# 04_-_PMIC-PWR_Monitor.net
KiCad netlist of a schematic drawn in Altium Designer
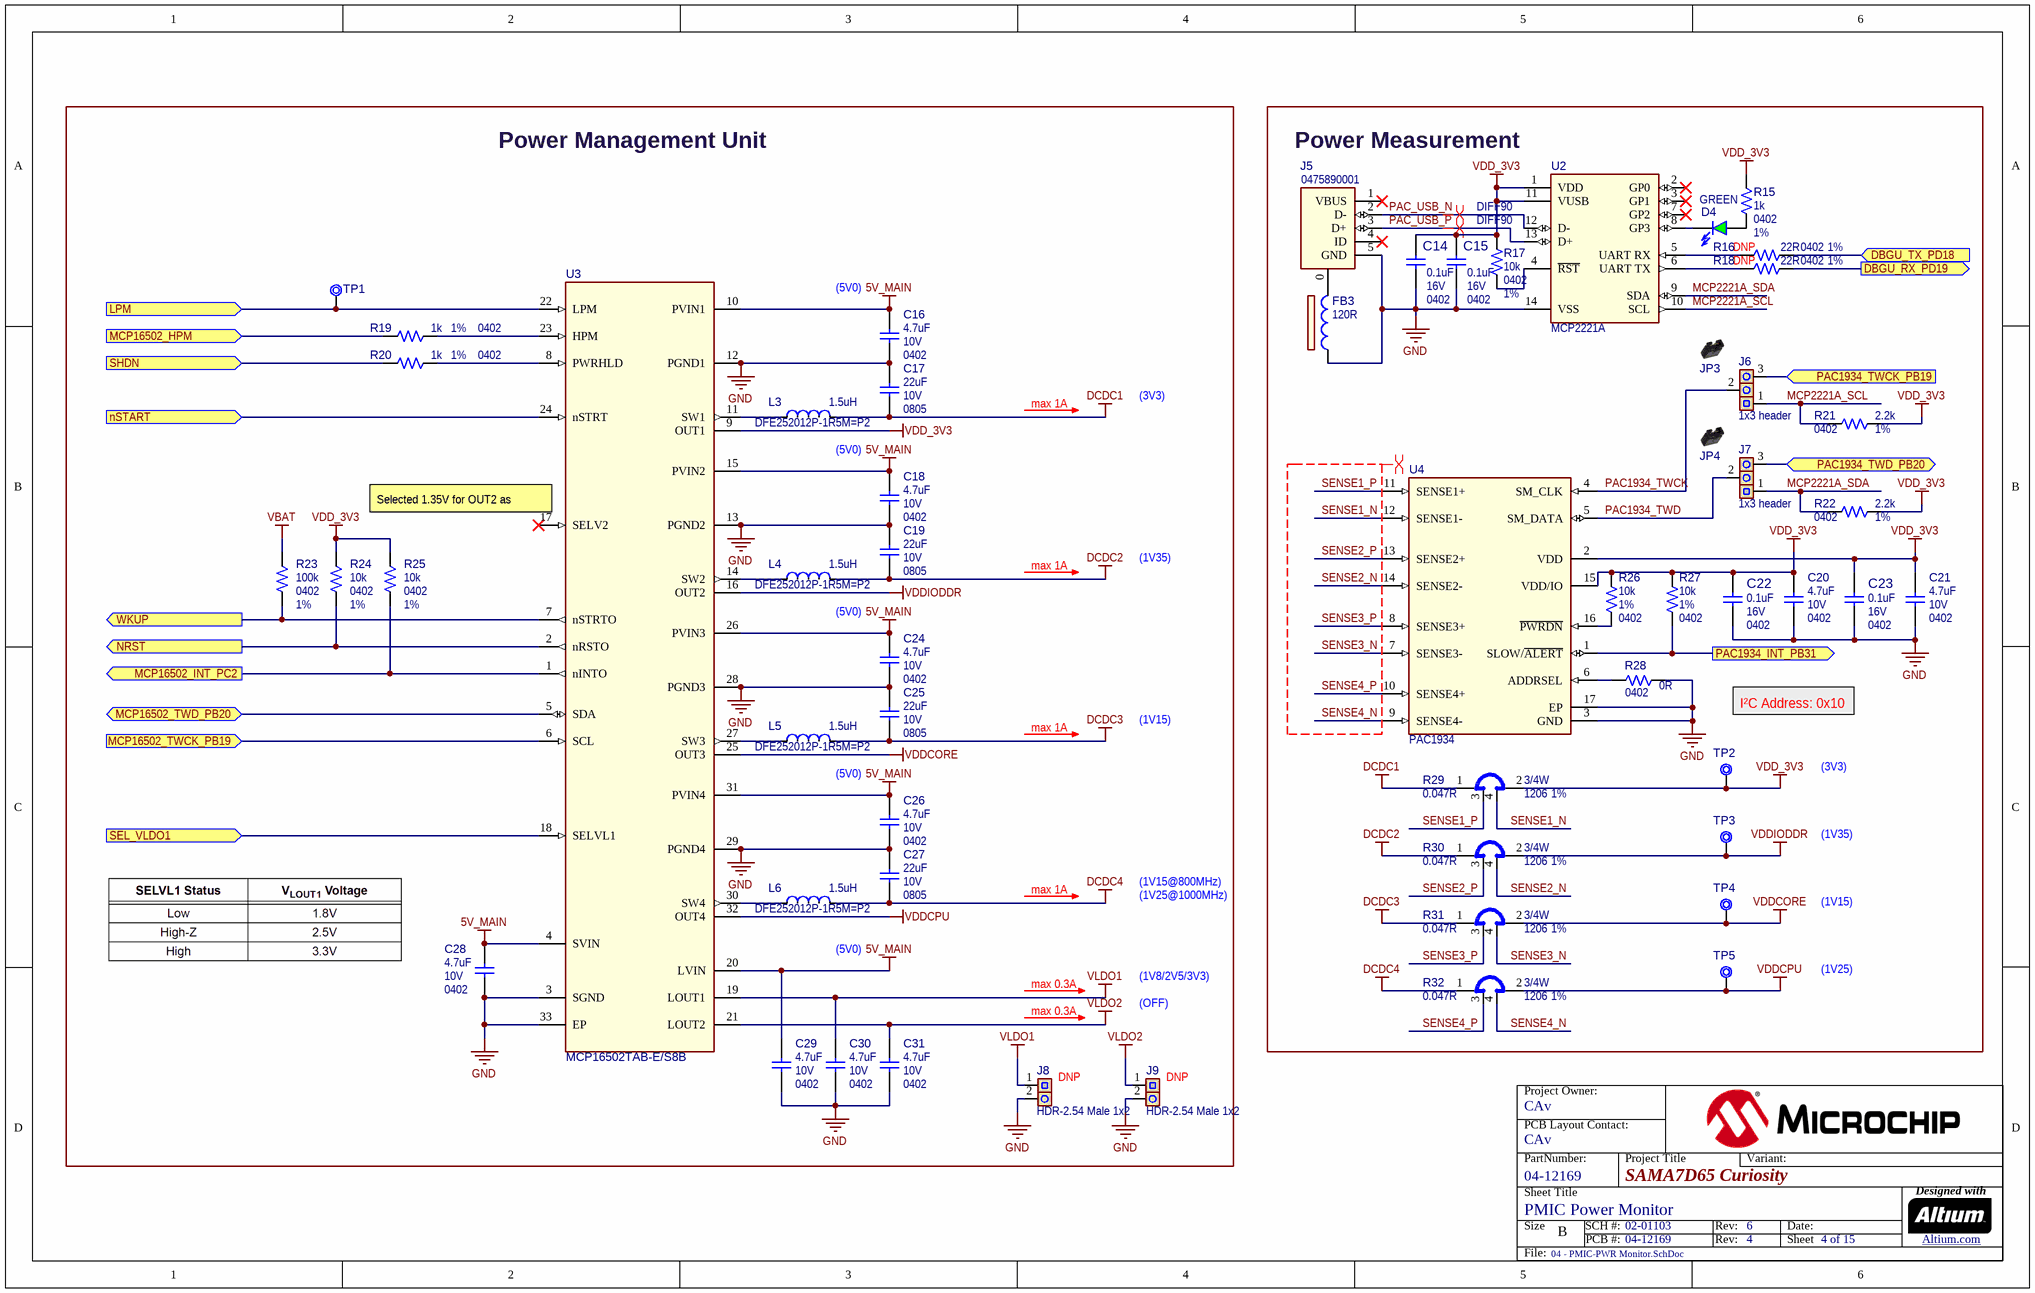
[diagram p0: 04 - PMIC-PWR Monitor.SchDoc]

(export (version "E")
  (design (tool "Eeschema 10.0.6"))
  (components
    (comp (ref "C14")
      (value "0.1uF")
      (footprint "CAP_C_0402")
      (fields
        (field (name "VOLTAGE") "16V")
        (field (name "PACKAGE") "0402")
        (field (name "TOLERANCE") "10%")
        (field (name "Comment") "Capacitor NP")
        (field (name "OWNER") "Sompoch Loboonlert")
      )
      (libsource (lib "MCHP-CDB") (part "Capacitor NP"))
    )
    (comp (ref "C15")
      (value "0.1uF")
      (footprint "CAP_C_0402")
      (fields
        (field (name "VOLTAGE") "16V")
        (field (name "PACKAGE") "0402")
        (field (name "TOLERANCE") "10%")
        (field (name "Comment") "Capacitor NP")
        (field (name "OWNER") "Sompoch Loboonlert")
      )
      (libsource (lib "MCHP-CDB") (part "Capacitor NP"))
    )
    (comp (ref "C16")
      (value "4.7uF")
      (footprint "CAP_C_0402")
      (description "Capacitor")
      (fields
        (field (name "VOLTAGE") "10V")
        (field (name "PACKAGE") "0402")
        (field (name "TOLERANCE") "10%")
        (field (name "Comment") "Capacitor NP")
        (field (name "OWNER") "Jesus Aviles")
      )
      (libsource (lib "") (part "Capacitor NP_1"))
    )
    (comp (ref "C17")
      (value "22uF")
      (footprint "CAP_C_0805")
      (fields
        (field (name "VOLTAGE") "10V")
        (field (name "PACKAGE") "0805")
        (field (name "TOLERANCE") "20%")
        (field (name "Comment") "Capacitor NP")
        (field (name "OWNER") "Razvan Cristescu")
      )
      (libsource (lib "MCHP-CDB") (part "Capacitor NP"))
    )
    (comp (ref "C18")
      (value "4.7uF")
      (footprint "CAP_C_0402")
      (description "Capacitor")
      (fields
        (field (name "VOLTAGE") "10V")
        (field (name "PACKAGE") "0402")
        (field (name "TOLERANCE") "10%")
        (field (name "Comment") "Capacitor NP")
        (field (name "OWNER") "Jesus Aviles")
      )
      (libsource (lib "") (part "Capacitor NP_1"))
    )
    (comp (ref "C19")
      (value "22uF")
      (footprint "CAP_C_0805")
      (fields
        (field (name "VOLTAGE") "10V")
        (field (name "PACKAGE") "0805")
        (field (name "TOLERANCE") "20%")
        (field (name "Comment") "Capacitor NP")
        (field (name "OWNER") "Razvan Cristescu")
      )
      (libsource (lib "MCHP-CDB") (part "Capacitor NP"))
    )
    (comp (ref "C20")
      (value "4.7uF")
      (footprint "CAP_C_0402")
      (description "Capacitor")
      (fields
        (field (name "VOLTAGE") "10V")
        (field (name "PACKAGE") "0402")
        (field (name "TOLERANCE") "10%")
        (field (name "Comment") "Capacitor NP")
        (field (name "OWNER") "Jesus Aviles")
      )
      (libsource (lib "") (part "Capacitor NP_1"))
    )
    (comp (ref "C21")
      (value "4.7uF")
      (footprint "CAP_C_0402")
      (description "Capacitor")
      (fields
        (field (name "VOLTAGE") "10V")
        (field (name "PACKAGE") "0402")
        (field (name "TOLERANCE") "10%")
        (field (name "Comment") "Capacitor NP")
        (field (name "OWNER") "Jesus Aviles")
      )
      (libsource (lib "") (part "Capacitor NP_1"))
    )
    (comp (ref "C22")
      (value "0.1uF")
      (footprint "CAP_C_0402")
      (fields
        (field (name "VOLTAGE") "16V")
        (field (name "PACKAGE") "0402")
        (field (name "TOLERANCE") "10%")
        (field (name "Comment") "Capacitor NP")
        (field (name "OWNER") "Sompoch Loboonlert")
      )
      (libsource (lib "MCHP-CDB") (part "Capacitor NP"))
    )
    (comp (ref "C23")
      (value "0.1uF")
      (footprint "CAP_C_0402")
      (fields
        (field (name "VOLTAGE") "16V")
        (field (name "PACKAGE") "0402")
        (field (name "TOLERANCE") "10%")
        (field (name "Comment") "Capacitor NP")
        (field (name "OWNER") "Sompoch Loboonlert")
      )
      (libsource (lib "MCHP-CDB") (part "Capacitor NP"))
    )
    (comp (ref "C24")
      (value "4.7uF")
      (footprint "CAP_C_0402")
      (description "Capacitor")
      (fields
        (field (name "VOLTAGE") "10V")
        (field (name "PACKAGE") "0402")
        (field (name "TOLERANCE") "10%")
        (field (name "Comment") "Capacitor NP")
        (field (name "OWNER") "Jesus Aviles")
      )
      (libsource (lib "") (part "Capacitor NP_1"))
    )
    (comp (ref "C25")
      (value "22uF")
      (footprint "CAP_C_0805")
      (fields
        (field (name "VOLTAGE") "10V")
        (field (name "PACKAGE") "0805")
        (field (name "TOLERANCE") "20%")
        (field (name "Comment") "Capacitor NP")
        (field (name "OWNER") "Razvan Cristescu")
      )
      (libsource (lib "MCHP-CDB") (part "Capacitor NP"))
    )
    (comp (ref "C26")
      (value "4.7uF")
      (footprint "CAP_C_0402")
      (description "Capacitor")
      (fields
        (field (name "VOLTAGE") "10V")
        (field (name "PACKAGE") "0402")
        (field (name "TOLERANCE") "10%")
        (field (name "Comment") "Capacitor NP")
        (field (name "OWNER") "Jesus Aviles")
      )
      (libsource (lib "") (part "Capacitor NP_1"))
    )
    (comp (ref "C27")
      (value "22uF")
      (footprint "CAP_C_0805")
      (fields
        (field (name "VOLTAGE") "10V")
        (field (name "PACKAGE") "0805")
        (field (name "TOLERANCE") "20%")
        (field (name "Comment") "Capacitor NP")
        (field (name "OWNER") "Razvan Cristescu")
      )
      (libsource (lib "MCHP-CDB") (part "Capacitor NP"))
    )
    (comp (ref "C28")
      (value "4.7uF")
      (footprint "CAP_C_0402")
      (description "Capacitor")
      (fields
        (field (name "VOLTAGE") "10V")
        (field (name "PACKAGE") "0402")
        (field (name "TOLERANCE") "10%")
        (field (name "Comment") "Capacitor NP")
        (field (name "OWNER") "Jesus Aviles")
      )
      (libsource (lib "") (part "Capacitor NP_1"))
    )
    (comp (ref "C29")
      (value "4.7uF")
      (footprint "CAP_C_0402")
      (description "Capacitor")
      (fields
        (field (name "VOLTAGE") "10V")
        (field (name "PACKAGE") "0402")
        (field (name "TOLERANCE") "10%")
        (field (name "Comment") "Capacitor NP")
        (field (name "OWNER") "Jesus Aviles")
      )
      (libsource (lib "") (part "Capacitor NP_1"))
    )
    (comp (ref "C30")
      (value "4.7uF")
      (footprint "CAP_C_0402")
      (description "Capacitor")
      (fields
        (field (name "VOLTAGE") "10V")
        (field (name "PACKAGE") "0402")
        (field (name "TOLERANCE") "10%")
        (field (name "Comment") "Capacitor NP")
        (field (name "OWNER") "Jesus Aviles")
      )
      (libsource (lib "") (part "Capacitor NP_1"))
    )
    (comp (ref "C31")
      (value "4.7uF")
      (footprint "CAP_C_0402")
      (description "Capacitor")
      (fields
        (field (name "VOLTAGE") "10V")
        (field (name "PACKAGE") "0402")
        (field (name "TOLERANCE") "10%")
        (field (name "Comment") "Capacitor NP")
        (field (name "OWNER") "Jesus Aviles")
      )
      (libsource (lib "") (part "Capacitor NP_1"))
    )
    (comp (ref "D4")
      (value "GREEN")
      (footprint "LED_0603_GREEN")
      (description "LED")
      (fields
        (field (name "POWER") "75mW")
        (field (name "Comment") "LED_green")
        (field (name "OWNER") "Tad Ahlvers")
      )
      (libsource (lib "MCHP-CDB") (part "LED_green"))
    )
    (comp (ref "FB3")
      (value "120R")
      (footprint "IND_C_0603")
      (fields (field (name "Comment") "Ferrite Bead") (field (name "OWNER") "Petnarong Chaijaroong"))
      (libsource (lib "MCHP-CDB") (part "Ferrite Bead"))
    )
    (comp (ref "J5")
      (value "0475890001")
      (footprint "CON_USB_Micro-AB_SMD_RA_MOLEX_0475890001")
      (fields
        (field (name "VOLTAGE") "30VAC")
        (field (name "Comment") "CON USB2.0 Mini_Micro")
        (field (name "OWNER") "Dragos Danaila")
      )
      (libsource (lib "MCHP-CDB") (part "CON USB2.0 Mini_Micro"))
    )
    (comp (ref "J6")
      (value "1x3 header")
      (footprint "HDR_M_2.54_1x3")
      (fields (field (name "Comment") "Header 1x3") (field (name "OWNER") "Dragos Danaila"))
      (libsource (lib "MCHP-CDB") (part "Header 1x3"))
    )
    (comp (ref "J7")
      (value "1x3 header")
      (footprint "HDR_M_2.54_1x3")
      (fields (field (name "Comment") "Header 1x3") (field (name "OWNER") "Dragos Danaila"))
      (libsource (lib "MCHP-CDB") (part "Header 1x3"))
    )
    (comp (ref "J8")
      (value "HDR-2.54 Male 1x2")
      (footprint "HDR_M_2.54_1x2")
      (fields
        (field (name "POPULATED") "DNP")
        (field (name "VOLTAGE") "250V")
        (field (name "Comment") "Header 1x2")
        (field (name "OWNER") "Narasimha Murthy")
      )
      (libsource (lib "MCHP-CDB") (part "Header 1x2"))
    )
    (comp (ref "J9")
      (value "HDR-2.54 Male 1x2")
      (footprint "HDR_M_2.54_1x2")
      (fields
        (field (name "POPULATED") "DNP")
        (field (name "VOLTAGE") "250V")
        (field (name "Comment") "Header 1x2")
        (field (name "OWNER") "Narasimha Murthy")
      )
      (libsource (lib "MCHP-CDB") (part "Header 1x2"))
    )
    (comp (ref "JP3")
      (value "Jumper Mechanical")
      (footprint "Jumper_Mechanical")
      (fields (field (name "OWNER") "Narasimha Murthy"))
      (libsource (lib "MCHP-CDB") (part "Jumper Mechanical"))
    )
    (comp (ref "JP4")
      (value "Jumper Mechanical")
      (footprint "Jumper_Mechanical")
      (fields (field (name "OWNER") "Narasimha Murthy"))
      (libsource (lib "MCHP-CDB") (part "Jumper Mechanical"))
    )
    (comp (ref "L3")
      (value "1.5uH")
      (footprint "IND_C_1008")
      (description "Inductor")
      (fields
        (field (name "MANUFACTURER PART NUMBER 1") "DFE252012P-1R5M=P2")
        (field (name "OWNER") "Razvan Cristescu")
      )
      (libsource (lib "MCHP-CDB") (part "Inductor"))
    )
    (comp (ref "L4")
      (value "1.5uH")
      (footprint "IND_C_1008")
      (description "Inductor")
      (fields
        (field (name "MANUFACTURER PART NUMBER 1") "DFE252012P-1R5M=P2")
        (field (name "OWNER") "Razvan Cristescu")
      )
      (libsource (lib "MCHP-CDB") (part "Inductor"))
    )
    (comp (ref "L5")
      (value "1.5uH")
      (footprint "IND_C_1008")
      (description "Inductor")
      (fields
        (field (name "MANUFACTURER PART NUMBER 1") "DFE252012P-1R5M=P2")
        (field (name "OWNER") "Razvan Cristescu")
      )
      (libsource (lib "MCHP-CDB") (part "Inductor"))
    )
    (comp (ref "L6")
      (value "1.5uH")
      (footprint "IND_C_1008")
      (description "Inductor")
      (fields
        (field (name "MANUFACTURER PART NUMBER 1") "DFE252012P-1R5M=P2")
        (field (name "OWNER") "Razvan Cristescu")
      )
      (libsource (lib "MCHP-CDB") (part "Inductor"))
    )
    (comp (ref "R15")
      (value "1k")
      (footprint "RES_C_0402")
      (description "Resistor")
      (fields
        (field (name "PACKAGE") "0402")
        (field (name "TOLERANCE") "1%")
        (field (name "VOLTAGE") "50V")
        (field (name "POWER") "1/10W")
        (field (name "OWNER") "Tad Ahlvers")
      )
      (libsource (lib "") (part "Resistor_1"))
    )
    (comp (ref "R16")
      (value "22R")
      (footprint "RES_C_0402")
      (description "Resistor")
      (fields
        (field (name "PACKAGE") "0402")
        (field (name "TOLERANCE") "1%")
        (field (name "POWER") "1/10W")
        (field (name "POPULATED") "DNP")
        (field (name "OWNER") "Mike Ragsdale")
      )
      (libsource (lib "MCHP-CDB") (part "Resistor"))
    )
    (comp (ref "R17")
      (value "10k")
      (footprint "RES_C_0402")
      (description "Resistor")
      (fields
        (field (name "PACKAGE") "0402")
        (field (name "TOLERANCE") "1%")
        (field (name "POWER") "1/10W")
        (field (name "VOLTAGE") "50V")
        (field (name "OWNER") "Brent Lanphear")
      )
      (libsource (lib "MCHP-CDB") (part "Resistor"))
    )
    (comp (ref "R18")
      (value "22R")
      (footprint "RES_C_0402")
      (description "Resistor")
      (fields
        (field (name "PACKAGE") "0402")
        (field (name "TOLERANCE") "1%")
        (field (name "POWER") "1/10W")
        (field (name "POPULATED") "DNP")
        (field (name "OWNER") "Mike Ragsdale")
      )
      (libsource (lib "MCHP-CDB") (part "Resistor"))
    )
    (comp (ref "R19")
      (value "1k")
      (footprint "RES_C_0402")
      (description "Resistor")
      (fields
        (field (name "PACKAGE") "0402")
        (field (name "TOLERANCE") "1%")
        (field (name "VOLTAGE") "50V")
        (field (name "POWER") "1/10W")
        (field (name "OWNER") "Tad Ahlvers")
      )
      (libsource (lib "") (part "Resistor_1"))
    )
    (comp (ref "R20")
      (value "1k")
      (footprint "RES_C_0402")
      (description "Resistor")
      (fields
        (field (name "PACKAGE") "0402")
        (field (name "TOLERANCE") "1%")
        (field (name "VOLTAGE") "50V")
        (field (name "POWER") "1/10W")
        (field (name "OWNER") "Tad Ahlvers")
      )
      (libsource (lib "") (part "Resistor_1"))
    )
    (comp (ref "R21")
      (value "2.2k")
      (footprint "RES_C_0402")
      (description "Resistor")
      (fields
        (field (name "PACKAGE") "0402")
        (field (name "TOLERANCE") "1%")
        (field (name "VOLTAGE") "50V")
        (field (name "POWER") "1/10W")
        (field (name "OWNER") "Tad Ahlvers")
      )
      (libsource (lib "MCHP-CDB") (part "Resistor"))
    )
    (comp (ref "R22")
      (value "2.2k")
      (footprint "RES_C_0402")
      (description "Resistor")
      (fields
        (field (name "PACKAGE") "0402")
        (field (name "TOLERANCE") "1%")
        (field (name "VOLTAGE") "50V")
        (field (name "POWER") "1/10W")
        (field (name "OWNER") "Tad Ahlvers")
      )
      (libsource (lib "MCHP-CDB") (part "Resistor"))
    )
    (comp (ref "R23")
      (value "100k")
      (footprint "RES_C_0402")
      (description "Resistor")
      (fields
        (field (name "PACKAGE") "0402")
        (field (name "TOLERANCE") "1%")
        (field (name "VOLTAGE") "50V")
        (field (name "POWER") "1/10W")
        (field (name "OWNER") "Tad Ahlvers")
      )
      (libsource (lib "") (part "Resistor_1"))
    )
    (comp (ref "R24")
      (value "10k")
      (footprint "RES_C_0402")
      (description "Resistor")
      (fields
        (field (name "PACKAGE") "0402")
        (field (name "TOLERANCE") "1%")
        (field (name "VOLTAGE") "50V")
        (field (name "POWER") "1/10W")
        (field (name "OWNER") "Brent Lanphear")
      )
      (libsource (lib "") (part "Resistor_1"))
    )
    (comp (ref "R25")
      (value "10k")
      (footprint "RES_C_0402")
      (description "Resistor")
      (fields
        (field (name "PACKAGE") "0402")
        (field (name "TOLERANCE") "1%")
        (field (name "VOLTAGE") "50V")
        (field (name "POWER") "1/10W")
        (field (name "OWNER") "Brent Lanphear")
      )
      (libsource (lib "") (part "Resistor_1"))
    )
    (comp (ref "R26")
      (value "10k")
      (footprint "RES_C_0402")
      (description "Resistor")
      (fields
        (field (name "PACKAGE") "0402")
        (field (name "TOLERANCE") "1%")
        (field (name "VOLTAGE") "50V")
        (field (name "POWER") "1/10W")
        (field (name "OWNER") "Brent Lanphear")
      )
      (libsource (lib "MCHP-CDB") (part "Resistor"))
    )
    (comp (ref "R27")
      (value "10k")
      (footprint "RES_C_0402")
      (description "Resistor")
      (fields
        (field (name "PACKAGE") "0402")
        (field (name "TOLERANCE") "1%")
        (field (name "VOLTAGE") "50V")
        (field (name "POWER") "1/10W")
        (field (name "OWNER") "Brent Lanphear")
      )
      (libsource (lib "MCHP-CDB") (part "Resistor"))
    )
    (comp (ref "R28")
      (value "0R")
      (footprint "RES_C_0402")
      (description "Resistor")
      (fields
        (field (name "PACKAGE") "0402")
        (field (name "POWER") "1/16W")
        (field (name "OWNER") "Sompoch Loboonlert")
      )
      (libsource (lib "") (part "Resistor_1"))
    )
    (comp (ref "R29")
      (value "0.047R")
      (footprint "RES_C_1206_SHUNT")
      (description "Shunt")
      (fields
        (field (name "PACKAGE") "1206")
        (field (name "TOLERANCE") "1%")
        (field (name "POWER") "3/4W")
        (field (name "Comment") "Shunt 4 Pin")
        (field (name "OWNER") "Ciprian Abramov")
      )
      (libsource (lib "MCHP-CDB") (part "Shunt 4 Pin"))
    )
    (comp (ref "R30")
      (value "0.047R")
      (footprint "RES_C_1206_SHUNT")
      (description "Shunt")
      (fields
        (field (name "PACKAGE") "1206")
        (field (name "TOLERANCE") "1%")
        (field (name "POWER") "3/4W")
        (field (name "Comment") "Shunt 4 Pin")
        (field (name "OWNER") "Ciprian Abramov")
      )
      (libsource (lib "MCHP-CDB") (part "Shunt 4 Pin"))
    )
    (comp (ref "R31")
      (value "0.047R")
      (footprint "RES_C_1206_SHUNT")
      (description "Shunt")
      (fields
        (field (name "PACKAGE") "1206")
        (field (name "TOLERANCE") "1%")
        (field (name "POWER") "3/4W")
        (field (name "Comment") "Shunt 4 Pin")
        (field (name "OWNER") "Ciprian Abramov")
      )
      (libsource (lib "MCHP-CDB") (part "Shunt 4 Pin"))
    )
    (comp (ref "R32")
      (value "0.047R")
      (footprint "RES_C_1206_SHUNT")
      (description "Shunt")
      (fields
        (field (name "PACKAGE") "1206")
        (field (name "TOLERANCE") "1%")
        (field (name "POWER") "3/4W")
        (field (name "Comment") "Shunt 4 Pin")
        (field (name "OWNER") "Ciprian Abramov")
      )
      (libsource (lib "MCHP-CDB") (part "Shunt 4 Pin"))
    )
    (comp (ref "TP1")
      (value "Test Point No BOM")
      (footprint "TP_1mm_SMD")
      (description "Test Point")
      (fields (field (name "OWNER") "Cristian Papuc"))
      (libsource (lib "MCHP-CDB") (part "Test Point No BOM"))
    )
    (comp (ref "TP2")
      (value "Test Point No BOM")
      (footprint "TP_1mm_SMD")
      (description "Test Point")
      (fields (field (name "OWNER") "Cristian Papuc"))
      (libsource (lib "MCHP-CDB") (part "Test Point No BOM"))
    )
    (comp (ref "TP3")
      (value "Test Point No BOM")
      (footprint "TP_1mm_SMD")
      (description "Test Point")
      (fields (field (name "OWNER") "Cristian Papuc"))
      (libsource (lib "MCHP-CDB") (part "Test Point No BOM"))
    )
    (comp (ref "TP4")
      (value "Test Point No BOM")
      (footprint "TP_1mm_SMD")
      (description "Test Point")
      (fields (field (name "OWNER") "Cristian Papuc"))
      (libsource (lib "MCHP-CDB") (part "Test Point No BOM"))
    )
    (comp (ref "TP5")
      (value "Test Point No BOM")
      (footprint "TP_1mm_SMD")
      (description "Test Point")
      (fields (field (name "OWNER") "Cristian Papuc"))
      (libsource (lib "MCHP-CDB") (part "Test Point No BOM"))
    )
    (comp (ref "U2")
      (value "MCP2221A")
      (footprint "SOIC-14")
      (fields
        (field (name "Comment") "MCP2221 SOIC-14_TSSOP-14_PDIP-14")
        (field (name "OWNER") "Octavian Stroe")
      )
      (libsource (lib "MCHP-CDB") (part "MCP2221 SOIC-14_TSSOP-14_PDIP-14"))
    )
    (comp (ref "U3")
      (value "MCP16502TAB-E/S8B")
      (footprint "QFN-32_5X5_EP3.7X3.7")
      (fields (field (name "Comment") "MCP16502 QFN-32") (field (name "OWNER") "Dragos Danaila"))
      (libsource (lib "MCHP-CDB") (part "MCP16502 QFN-32"))
    )
    (comp (ref "U4")
      (value "PAC1934")
      (footprint "UQFN-16_4X4_EP2.6X2.6")
      (fields (field (name "Comment") "PAC1934 UQFN-16") (field (name "OWNER") "Razvan Cristescu"))
      (libsource (lib "MCHP-CDB") (part "PAC1934 UQFN-16"))
    )
  )
  (nets
    (net (code "1") (name "/DBGU_RX_PD19") (class "Default")
      (node (ref "R18") (pin "1") (pinfunction "1_1") (pintype "passive"))
    )
    (net (code "2") (name "/DBGU_TX_PD18") (class "Default")
      (node (ref "R16") (pin "1") (pinfunction "1_1") (pintype "passive"))
    )
    (net (code "3") (name "/LPM") (class "Default")
      (node (ref "TP1") (pin "1") (pinfunction "1_1") (pintype "passive"))
      (node (ref "U3") (pin "22") (pinfunction "LPM_22") (pintype "input"))
    )
    (net (code "4") (name "/MCP2221A_SCL") (class "Default")
      (node (ref "J6") (pin "1") (pinfunction "1_1") (pintype "passive"))
      (node (ref "R21") (pin "2") (pinfunction "2_2") (pintype "passive"))
      (node (ref "U2") (pin "10") (pinfunction "SCL_10") (pintype "output"))
    )
    (net (code "5") (name "/MCP2221A_SDA") (class "Default")
      (node (ref "J7") (pin "1") (pinfunction "1_1") (pintype "passive"))
      (node (ref "R22") (pin "2") (pinfunction "2_2") (pintype "passive"))
      (node (ref "U2") (pin "9") (pinfunction "SDA_9") (pintype "bidirectional"))
    )
    (net (code "6") (name "/MCP16502_HPM") (class "Default")
      (node (ref "R19") (pin "1") (pinfunction "1_1") (pintype "passive"))
    )
    (net (code "7") (name "/MCP16502_INT_PC2") (class "Default")
      (node (ref "R25") (pin "1") (pinfunction "1_1") (pintype "passive"))
      (node (ref "U3") (pin "1") (pinfunction "nINTO_1") (pintype "output"))
    )
    (net (code "8") (name "/MCP16502_TWCK_PB19") (class "Default")
      (node (ref "U3") (pin "6") (pinfunction "SCL_6") (pintype "input"))
    )
    (net (code "9") (name "/MCP16502_TWD_PB20") (class "Default")
      (node (ref "U3") (pin "5") (pinfunction "SDA_5") (pintype "bidirectional"))
    )
    (net (code "10") (name "/NRST") (class "Default")
      (node (ref "R24") (pin "1") (pinfunction "1_1") (pintype "passive"))
      (node (ref "U3") (pin "2") (pinfunction "nRSTO_2") (pintype "output"))
    )
    (net (code "11") (name "/PAC1934_INT_PB31") (class "Default")
      (node (ref "R27") (pin "1") (pinfunction "1_1") (pintype "passive"))
      (node (ref "U4") (pin "1") (pinfunction "SLOW/~{ALERT}_1") (pintype "bidirectional"))
    )
    (net (code "12") (name "/PAC1934_TWCK") (class "Default")
      (node (ref "J6") (pin "2") (pinfunction "2_2") (pintype "passive"))
      (node (ref "U4") (pin "4") (pinfunction "SM_CLK_4") (pintype "input"))
    )
    (net (code "13") (name "/PAC1934_TWCK_PB19") (class "Default")
      (node (ref "J6") (pin "3") (pinfunction "3_3") (pintype "passive"))
    )
    (net (code "14") (name "/PAC1934_TWD") (class "Default")
      (node (ref "J7") (pin "2") (pinfunction "2_2") (pintype "passive"))
      (node (ref "U4") (pin "5") (pinfunction "SM_DATA_5") (pintype "bidirectional"))
    )
    (net (code "15") (name "/PAC1934_TWD_PB20") (class "Default")
      (node (ref "J7") (pin "3") (pinfunction "3_3") (pintype "passive"))
    )
    (net (code "16") (name "/PAC_USB_N") (class "Default")
      (node (ref "J5") (pin "2") (pinfunction "D-_2") (pintype "bidirectional"))
      (node (ref "U2") (pin "12") (pinfunction "D-_12") (pintype "bidirectional"))
    )
    (net (code "17") (name "/PAC_USB_P") (class "Default")
      (node (ref "J5") (pin "3") (pinfunction "D+_3") (pintype "bidirectional"))
      (node (ref "U2") (pin "13") (pinfunction "D+_13") (pintype "bidirectional"))
    )
    (net (code "18") (name "/SEL_VLDO1") (class "Default")
      (node (ref "U3") (pin "18") (pinfunction "SELVL1_18") (pintype "input"))
    )
    (net (code "19") (name "/SENSE1_N") (class "Default")
      (node (ref "R29") (pin "4") (pinfunction "4_4") (pintype "passive"))
      (node (ref "U4") (pin "12") (pinfunction "SENSE1-_12") (pintype "input"))
    )
    (net (code "20") (name "/SENSE1_P") (class "Default")
      (node (ref "R29") (pin "3") (pinfunction "3_3") (pintype "passive"))
      (node (ref "U4") (pin "11") (pinfunction "SENSE1+_11") (pintype "input"))
    )
    (net (code "21") (name "/SENSE2_N") (class "Default")
      (node (ref "R30") (pin "4") (pinfunction "4_4") (pintype "passive"))
      (node (ref "U4") (pin "14") (pinfunction "SENSE2-_14") (pintype "input"))
    )
    (net (code "22") (name "/SENSE2_P") (class "Default")
      (node (ref "R30") (pin "3") (pinfunction "3_3") (pintype "passive"))
      (node (ref "U4") (pin "13") (pinfunction "SENSE2+_13") (pintype "input"))
    )
    (net (code "23") (name "/SENSE3_N") (class "Default")
      (node (ref "R31") (pin "4") (pinfunction "4_4") (pintype "passive"))
      (node (ref "U4") (pin "7") (pinfunction "SENSE3-_7") (pintype "input"))
    )
    (net (code "24") (name "/SENSE3_P") (class "Default")
      (node (ref "R31") (pin "3") (pinfunction "3_3") (pintype "passive"))
      (node (ref "U4") (pin "8") (pinfunction "SENSE3+_8") (pintype "input"))
    )
    (net (code "25") (name "/SENSE4_N") (class "Default")
      (node (ref "R32") (pin "4") (pinfunction "4_4") (pintype "passive"))
      (node (ref "U4") (pin "9") (pinfunction "SENSE4-_9") (pintype "input"))
    )
    (net (code "26") (name "/SENSE4_P") (class "Default")
      (node (ref "R32") (pin "3") (pinfunction "3_3") (pintype "passive"))
      (node (ref "U4") (pin "10") (pinfunction "SENSE4+_10") (pintype "input"))
    )
    (net (code "27") (name "/SHDN") (class "Default")
      (node (ref "R20") (pin "1") (pinfunction "1_1") (pintype "passive"))
    )
    (net (code "28") (name "/WKUP") (class "Default")
      (node (ref "R23") (pin "1") (pinfunction "1_1") (pintype "passive"))
      (node (ref "U3") (pin "7") (pinfunction "nSTRTO_7") (pintype "output"))
    )
    (net (code "29") (name "/nSTART") (class "Default")
      (node (ref "U3") (pin "24") (pinfunction "nSTRT_24") (pintype "input"))
    )
    (net (code "30") (name "5V_MAIN") (class "Default")
      (node (ref "C16") (pin "2") (pinfunction "2_2") (pintype "passive"))
      (node (ref "C18") (pin "2") (pinfunction "2_2") (pintype "passive"))
      (node (ref "C24") (pin "2") (pinfunction "2_2") (pintype "passive"))
      (node (ref "C26") (pin "2") (pinfunction "2_2") (pintype "passive"))
      (node (ref "C28") (pin "2") (pinfunction "2_2") (pintype "passive"))
      (node (ref "C29") (pin "2") (pinfunction "2_2") (pintype "passive"))
      (node (ref "U3") (pin "10") (pinfunction "PVIN1_10") (pintype "power_in"))
      (node (ref "U3") (pin "15") (pinfunction "PVIN2_15") (pintype "power_in"))
      (node (ref "U3") (pin "20") (pinfunction "LVIN_20") (pintype "power_in"))
      (node (ref "U3") (pin "26") (pinfunction "PVIN3_26") (pintype "power_in"))
      (node (ref "U3") (pin "31") (pinfunction "PVIN4_31") (pintype "power_in"))
      (node (ref "U3") (pin "4") (pinfunction "SVIN_4") (pintype "power_in"))
    )
    (net (code "31") (name "DCDC1") (class "Default")
      (node (ref "C17") (pin "1") (pinfunction "1_1") (pintype "passive"))
      (node (ref "L3") (pin "2") (pinfunction "F_2") (pintype "passive"))
      (node (ref "R29") (pin "1") (pinfunction "1_1") (pintype "passive"))
    )
    (net (code "32") (name "DCDC2") (class "Default")
      (node (ref "C19") (pin "1") (pinfunction "1_1") (pintype "passive"))
      (node (ref "L4") (pin "2") (pinfunction "F_2") (pintype "passive"))
      (node (ref "R30") (pin "1") (pinfunction "1_1") (pintype "passive"))
    )
    (net (code "33") (name "DCDC3") (class "Default")
      (node (ref "C25") (pin "1") (pinfunction "1_1") (pintype "passive"))
      (node (ref "L5") (pin "2") (pinfunction "F_2") (pintype "passive"))
      (node (ref "R31") (pin "1") (pinfunction "1_1") (pintype "passive"))
    )
    (net (code "34") (name "DCDC4") (class "Default")
      (node (ref "C27") (pin "1") (pinfunction "1_1") (pintype "passive"))
      (node (ref "L6") (pin "2") (pinfunction "F_2") (pintype "passive"))
      (node (ref "R32") (pin "1") (pinfunction "1_1") (pintype "passive"))
    )
    (net (code "35") (name "GND") (class "Default")
      (node (ref "C14") (pin "2") (pinfunction "2_2") (pintype "passive"))
      (node (ref "C15") (pin "2") (pinfunction "2_2") (pintype "passive"))
      (node (ref "C16") (pin "1") (pinfunction "1_1") (pintype "passive"))
      (node (ref "C17") (pin "2") (pinfunction "2_2") (pintype "passive"))
      (node (ref "C18") (pin "1") (pinfunction "1_1") (pintype "passive"))
      (node (ref "C19") (pin "2") (pinfunction "2_2") (pintype "passive"))
      (node (ref "C20") (pin "1") (pinfunction "1_1") (pintype "passive"))
      (node (ref "C21") (pin "1") (pinfunction "1_1") (pintype "passive"))
      (node (ref "C22") (pin "1") (pinfunction "1_1") (pintype "passive"))
      (node (ref "C23") (pin "1") (pinfunction "1_1") (pintype "passive"))
      (node (ref "C24") (pin "1") (pinfunction "1_1") (pintype "passive"))
      (node (ref "C25") (pin "2") (pinfunction "2_2") (pintype "passive"))
      (node (ref "C26") (pin "1") (pinfunction "1_1") (pintype "passive"))
      (node (ref "C27") (pin "2") (pinfunction "2_2") (pintype "passive"))
      (node (ref "C28") (pin "1") (pinfunction "1_1") (pintype "passive"))
      (node (ref "C29") (pin "1") (pinfunction "1_1") (pintype "passive"))
      (node (ref "C30") (pin "1") (pinfunction "1_1") (pintype "passive"))
      (node (ref "C31") (pin "1") (pinfunction "1_1") (pintype "passive"))
      (node (ref "FB3") (pin "1") (pinfunction "1_1") (pintype "passive"))
      (node (ref "J5") (pin "5") (pinfunction "GND_5") (pintype "power_in"))
      (node (ref "J8") (pin "2") (pinfunction "2_2") (pintype "passive"))
      (node (ref "J9") (pin "2") (pinfunction "2_2") (pintype "passive"))
      (node (ref "R28") (pin "2") (pinfunction "2_2") (pintype "passive"))
      (node (ref "U2") (pin "14") (pinfunction "VSS_14") (pintype "power_in"))
      (node (ref "U3") (pin "12") (pinfunction "PGND1_12") (pintype "power_in"))
      (node (ref "U3") (pin "13") (pinfunction "PGND2_13") (pintype "power_in"))
      (node (ref "U3") (pin "28") (pinfunction "PGND3_28") (pintype "power_in"))
      (node (ref "U3") (pin "29") (pinfunction "PGND4_29") (pintype "power_in"))
      (node (ref "U3") (pin "3") (pinfunction "SGND_3") (pintype "power_in"))
      (node (ref "U3") (pin "33") (pinfunction "EP_33") (pintype "power_in"))
      (node (ref "U4") (pin "17") (pinfunction "EP_17") (pintype "passive"))
      (node (ref "U4") (pin "3") (pinfunction "GND_3") (pintype "power_in"))
    )
    (net (code "36") (name "Net-(D4-A)") (class "Default")
      (node (ref "D4") (pin "1") (pinfunction "A_1") (pintype "passive"))
      (node (ref "R15") (pin "1") (pinfunction "1_1") (pintype "passive"))
    )
    (net (code "37") (name "Net-(D4-K)") (class "Default")
      (node (ref "D4") (pin "2") (pinfunction "K_2") (pintype "passive"))
      (node (ref "U2") (pin "8") (pinfunction "GP3_8") (pintype "bidirectional"))
    )
    (net (code "38") (name "Net-(J5-SHLD)") (class "Default")
      (node (ref "FB3") (pin "2") (pinfunction "2_2") (pintype "passive"))
      (node (ref "J5") (pin "0") (pinfunction "SHLD_0") (pintype "passive"))
    )
    (net (code "39") (name "Net-(L3-S)") (class "Default")
      (node (ref "L3") (pin "1") (pinfunction "S_1") (pintype "passive"))
      (node (ref "U3") (pin "11") (pinfunction "SW1_11") (pintype "output"))
    )
    (net (code "40") (name "Net-(L4-S)") (class "Default")
      (node (ref "L4") (pin "1") (pinfunction "S_1") (pintype "passive"))
      (node (ref "U3") (pin "14") (pinfunction "SW2_14") (pintype "output"))
    )
    (net (code "41") (name "Net-(L5-S)") (class "Default")
      (node (ref "L5") (pin "1") (pinfunction "S_1") (pintype "passive"))
      (node (ref "U3") (pin "27") (pinfunction "SW3_27") (pintype "output"))
    )
    (net (code "42") (name "Net-(L6-S)") (class "Default")
      (node (ref "L6") (pin "1") (pinfunction "S_1") (pintype "passive"))
      (node (ref "U3") (pin "30") (pinfunction "SW4_30") (pintype "output"))
    )
    (net (code "43") (name "Net-(U2-UART_RX)") (class "Default")
      (node (ref "R16") (pin "2") (pinfunction "2_2") (pintype "passive"))
      (node (ref "U2") (pin "5") (pinfunction "UART_RX_5") (pintype "input"))
    )
    (net (code "44") (name "Net-(U2-UART_TX)") (class "Default")
      (node (ref "R18") (pin "2") (pinfunction "2_2") (pintype "passive"))
      (node (ref "U2") (pin "6") (pinfunction "UART_TX_6") (pintype "output"))
    )
    (net (code "45") (name "Net-(U2-~{RST})") (class "Default")
      (node (ref "R17") (pin "1") (pinfunction "1_1") (pintype "passive"))
      (node (ref "U2") (pin "4") (pinfunction "~{RST}_4") (pintype "passive"))
    )
    (net (code "46") (name "Net-(U3-HPM)") (class "Default")
      (node (ref "R19") (pin "2") (pinfunction "2_2") (pintype "passive"))
      (node (ref "U3") (pin "23") (pinfunction "HPM_23") (pintype "input"))
    )
    (net (code "47") (name "Net-(U3-PWRHLD)") (class "Default")
      (node (ref "R20") (pin "2") (pinfunction "2_2") (pintype "passive"))
      (node (ref "U3") (pin "8") (pinfunction "PWRHLD_8") (pintype "input"))
    )
    (net (code "48") (name "Net-(U4-ADDRSEL)") (class "Default")
      (node (ref "R28") (pin "1") (pinfunction "1_1") (pintype "passive"))
      (node (ref "U4") (pin "6") (pinfunction "ADDRSEL_6") (pintype "input"))
    )
    (net (code "49") (name "Net-(U4-~{PWRDN})") (class "Default")
      (node (ref "R26") (pin "1") (pinfunction "1_1") (pintype "passive"))
      (node (ref "U4") (pin "16") (pinfunction "~{PWRDN}_16") (pintype "input"))
    )
    (net (code "50") (name "VBAT") (class "Default")
      (node (ref "R23") (pin "2") (pinfunction "2_2") (pintype "passive"))
    )
    (net (code "51") (name "VDDCORE") (class "Default")
      (node (ref "R31") (pin "2") (pinfunction "2_2") (pintype "passive"))
      (node (ref "TP4") (pin "1") (pinfunction "1_1") (pintype "passive"))
      (node (ref "U3") (pin "25") (pinfunction "OUT3_25") (pintype "power_in"))
    )
    (net (code "52") (name "VDDCPU") (class "Default")
      (node (ref "R32") (pin "2") (pinfunction "2_2") (pintype "passive"))
      (node (ref "TP5") (pin "1") (pinfunction "1_1") (pintype "passive"))
      (node (ref "U3") (pin "32") (pinfunction "OUT4_32") (pintype "power_in"))
    )
    (net (code "53") (name "VDDIODDR") (class "Default")
      (node (ref "R30") (pin "2") (pinfunction "2_2") (pintype "passive"))
      (node (ref "TP3") (pin "1") (pinfunction "1_1") (pintype "passive"))
      (node (ref "U3") (pin "16") (pinfunction "OUT2_16") (pintype "power_in"))
    )
    (net (code "54") (name "VDD_3V3") (class "Default")
      (node (ref "C14") (pin "1") (pinfunction "1_1") (pintype "passive"))
      (node (ref "C15") (pin "1") (pinfunction "1_1") (pintype "passive"))
      (node (ref "C20") (pin "2") (pinfunction "2_2") (pintype "passive"))
      (node (ref "C21") (pin "2") (pinfunction "2_2") (pintype "passive"))
      (node (ref "C22") (pin "2") (pinfunction "2_2") (pintype "passive"))
      (node (ref "C23") (pin "2") (pinfunction "2_2") (pintype "passive"))
      (node (ref "R15") (pin "2") (pinfunction "2_2") (pintype "passive"))
      (node (ref "R17") (pin "2") (pinfunction "2_2") (pintype "passive"))
      (node (ref "R21") (pin "1") (pinfunction "1_1") (pintype "passive"))
      (node (ref "R22") (pin "1") (pinfunction "1_1") (pintype "passive"))
      (node (ref "R24") (pin "2") (pinfunction "2_2") (pintype "passive"))
      (node (ref "R25") (pin "2") (pinfunction "2_2") (pintype "passive"))
      (node (ref "R26") (pin "2") (pinfunction "2_2") (pintype "passive"))
      (node (ref "R27") (pin "2") (pinfunction "2_2") (pintype "passive"))
      (node (ref "R29") (pin "2") (pinfunction "2_2") (pintype "passive"))
      (node (ref "TP2") (pin "1") (pinfunction "1_1") (pintype "passive"))
      (node (ref "U2") (pin "1") (pinfunction "VDD_1") (pintype "power_in"))
      (node (ref "U2") (pin "11") (pinfunction "VUSB_11") (pintype "power_in"))
      (node (ref "U3") (pin "9") (pinfunction "OUT1_9") (pintype "power_in"))
      (node (ref "U4") (pin "15") (pinfunction "VDD/IO_15") (pintype "power_in"))
      (node (ref "U4") (pin "2") (pinfunction "VDD_2") (pintype "power_in"))
    )
    (net (code "55") (name "VLDO1") (class "Default")
      (node (ref "C30") (pin "2") (pinfunction "2_2") (pintype "passive"))
      (node (ref "J8") (pin "1") (pinfunction "1_1") (pintype "passive"))
      (node (ref "U3") (pin "19") (pinfunction "LOUT1_19") (pintype "power_in"))
    )
    (net (code "56") (name "VLDO2") (class "Default")
      (node (ref "C31") (pin "2") (pinfunction "2_2") (pintype "passive"))
      (node (ref "J9") (pin "1") (pinfunction "1_1") (pintype "passive"))
      (node (ref "U3") (pin "21") (pinfunction "LOUT2_21") (pintype "power_in"))
    )
    (net (code "57") (name "unconnected-(J5-ID-Pad4)") (class "Default")
      (node (ref "J5") (pin "4") (pinfunction "ID_4") (pintype "passive+no_connect"))
    )
    (net (code "58") (name "unconnected-(J5-VBUS-Pad1)") (class "Default")
      (node (ref "J5") (pin "1") (pinfunction "VBUS_1") (pintype "power_in+no_connect"))
    )
    (net (code "59") (name "unconnected-(U2-GP0-Pad2)") (class "Default")
      (node (ref "U2") (pin "2") (pinfunction "GP0_2") (pintype "bidirectional+no_connect"))
    )
    (net (code "60") (name "unconnected-(U2-GP1-Pad3)") (class "Default")
      (node (ref "U2") (pin "3") (pinfunction "GP1_3") (pintype "bidirectional+no_connect"))
    )
    (net (code "61") (name "unconnected-(U2-GP2-Pad7)") (class "Default")
      (node (ref "U2") (pin "7") (pinfunction "GP2_7") (pintype "bidirectional+no_connect"))
    )
    (net (code "62") (name "unconnected-(U3-SELV2-Pad17)") (class "Default")
      (node (ref "U3") (pin "17") (pinfunction "SELV2_17") (pintype "input+no_connect"))
    )
  )
)
